# PowerSupply.net
KiCad netlist of a schematic drawn in Altium Designer
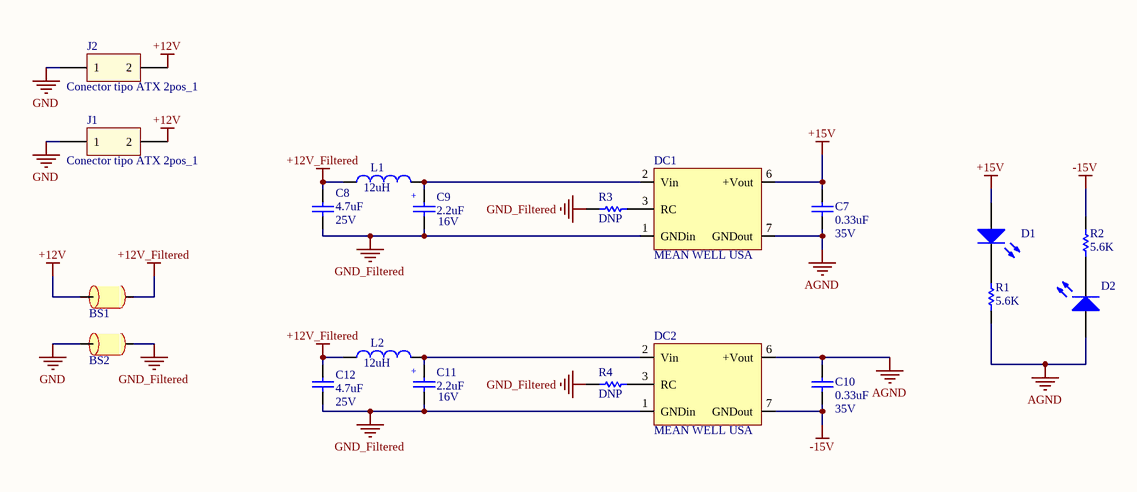
[diagram p0: PowerSupply.SchDoc]

(export (version "E")
  (design (tool "Eeschema 10.0.6"))
  (components
    (comp (ref "BS1")
      (value "Ferrite bead")
      (footprint "RES_1206")
      (description "4A")
      (libsource (lib "Componentes_SOC") (part "Bead"))
    )
    (comp (ref "BS2")
      (value "Ferrite bead")
      (footprint "RES_1206")
      (description "4A")
      (libsource (lib "Componentes_SOC") (part "Bead"))
    )
    (comp (ref "C7")
      (value "0.33uF")
      (footprint "CAP_0603")
      (description "Capacitor Ceramic")
      (fields (field (name "VOLTAGE") "35V"))
      (libsource (lib "Componentes_SOC") (part "Cap_0603"))
    )
    (comp (ref "C8")
      (value "4.7uF")
      (footprint "CAP_0805")
      (description "Capacitor")
      (fields (field (name "VOLTAGE") "25V"))
      (libsource (lib "Componentes_SOC") (part "Cap_0805"))
    )
    (comp (ref "C9")
      (value "2.2uF")
      (footprint "CAP_1206 Tantalio")
      (description "Capacitor Tantalio")
      (fields (field (name "VOLTAGE") "16V"))
      (libsource (lib "Componentes_SOC") (part "Cap Tantalio 1206"))
    )
    (comp (ref "C10")
      (value "0.33uF")
      (footprint "CAP_0603")
      (description "Capacitor Ceramic")
      (fields (field (name "VOLTAGE") "35V"))
      (libsource (lib "Componentes_SOC") (part "Cap_0603"))
    )
    (comp (ref "C11")
      (value "2.2uF")
      (footprint "CAP_1206 Tantalio")
      (description "Capacitor Tantalio")
      (fields (field (name "VOLTAGE") "16V"))
      (libsource (lib "Componentes_SOC") (part "Cap Tantalio 1206"))
    )
    (comp (ref "C12")
      (value "4.7uF")
      (footprint "CAP_0805")
      (description "Capacitor")
      (fields (field (name "VOLTAGE") "25V"))
      (libsource (lib "Componentes_SOC") (part "Cap_0805"))
    )
    (comp (ref "D1")
      (value "LED")
      (footprint "LED_0805_GREEN")
      (description "LED azul")
      (fields (field (name "PUBLISHER") "Altium Limited"))
      (libsource (lib "Componentes_SOC") (part "LED2"))
    )
    (comp (ref "D2")
      (value "LED")
      (footprint "LED_0805_GREEN")
      (description "LED Azul")
      (fields (field (name "PUBLISHER") "Altium Limited"))
      (libsource (lib "Componentes_SOC") (part "LED2"))
    )
    (comp (ref "DC1")
      (value "MEAN WELL USA")
      (footprint "DC/DC 15V 5W")
      (description "Isolated Module DC DC Converter 1 Output 15V 333mA 9V - 18V Input")
      (libsource (lib "Componentes_SOC") (part "DC/DC +12V a +15V 5W"))
    )
    (comp (ref "DC2")
      (value "MEAN WELL USA")
      (footprint "DC/DC 15V 5W")
      (description "Isolated Module DC DC Converter 1 Output 15V 333mA 9V - 18V Input")
      (libsource (lib "Componentes_SOC") (part "DC/DC +12V a +15V 5W"))
    )
    (comp (ref "J1")
      (value "Conector tipo ATX 2pos_1")
      (footprint "Conector tipo ATX Wurth 2 posiciones - (5.5mm)")
      (description "CONN HEADER VERT 2POS 5.5MM")
      (libsource (lib "Componentes_SOC") (part "Conector tipo ATX 2pos_1"))
    )
    (comp (ref "J2")
      (value "Conector tipo ATX 2pos_1")
      (footprint "Conector tipo ATX Wurth 2 posiciones - (5.5mm)")
      (description "CONN HEADER VERT 2POS 5.5MM")
      (libsource (lib "Componentes_SOC") (part "Conector tipo ATX 2pos_1"))
    )
    (comp (ref "L1")
      (value "12uH")
      (footprint "INDUCTOR_0805")
      (description "200mA")
      (libsource (lib "Componentes_SOC") (part "Inductor_0805"))
    )
    (comp (ref "L2")
      (value "12uH")
      (footprint "INDUCTOR_0805")
      (description "200mA")
      (libsource (lib "Componentes_SOC") (part "Inductor_0805"))
    )
    (comp (ref "R1")
      (value "5.6K")
      (footprint "RES_0805")
      (fields (field (name "PUBLISHER") "Altium Limited"))
      (libsource (lib "Componentes_SOC") (part "Res0805"))
    )
    (comp (ref "R2")
      (value "5.6K")
      (footprint "RES_0805")
      (fields (field (name "PUBLISHER") "Altium Limited"))
      (libsource (lib "Componentes_SOC") (part "Res0805"))
    )
    (comp (ref "R3")
      (value "DNP")
      (footprint "RES_0603")
      (libsource (lib "Componentes_SOC") (part "Res0603"))
    )
    (comp (ref "R4")
      (value "DNP")
      (footprint "RES_0603")
      (libsource (lib "Componentes_SOC") (part "Res0603"))
    )
  )
  (nets
    (net (code "1") (name "+12V") (class "Default")
      (node (ref "BS1") (pin "1") (pintype "passive"))
      (node (ref "J1") (pin "2") (pinfunction "2_2") (pintype "passive"))
      (node (ref "J2") (pin "2") (pinfunction "2_2") (pintype "passive"))
    )
    (net (code "2") (name "+12V_Filtered") (class "Default")
      (node (ref "BS1") (pin "2") (pintype "passive"))
      (node (ref "C12") (pin "1") (pinfunction "1_1") (pintype "passive"))
      (node (ref "C8") (pin "1") (pinfunction "1_1") (pintype "passive"))
      (node (ref "L1") (pin "1") (pinfunction "1_1") (pintype "passive"))
      (node (ref "L2") (pin "1") (pinfunction "1_1") (pintype "passive"))
    )
    (net (code "3") (name "+15V") (class "Default")
      (node (ref "C7") (pin "1") (pinfunction "1_1") (pintype "passive"))
      (node (ref "D1") (pin "1") (pinfunction "A_1") (pintype "passive"))
      (node (ref "DC1") (pin "6") (pinfunction "+Vout_6") (pintype "passive"))
    )
    (net (code "4") (name "-15V") (class "Default")
      (node (ref "C10") (pin "2") (pinfunction "2_2") (pintype "passive"))
      (node (ref "DC2") (pin "7") (pinfunction "GNDout_7") (pintype "passive"))
      (node (ref "R2") (pin "2") (pinfunction "2_2") (pintype "passive"))
    )
    (net (code "5") (name "AGND") (class "Default")
      (node (ref "C10") (pin "1") (pinfunction "1_1") (pintype "passive"))
      (node (ref "C7") (pin "2") (pinfunction "2_2") (pintype "passive"))
      (node (ref "D2") (pin "1") (pinfunction "A_1") (pintype "passive"))
      (node (ref "DC1") (pin "7") (pinfunction "GNDout_7") (pintype "passive"))
      (node (ref "DC2") (pin "6") (pinfunction "+Vout_6") (pintype "passive"))
      (node (ref "R1") (pin "1") (pinfunction "1_1") (pintype "passive"))
    )
    (net (code "6") (name "GND") (class "Default")
      (node (ref "BS2") (pin "1") (pintype "passive"))
      (node (ref "J1") (pin "1") (pinfunction "1_1") (pintype "passive"))
      (node (ref "J2") (pin "1") (pinfunction "1_1") (pintype "passive"))
    )
    (net (code "7") (name "GND_Filtered") (class "Default")
      (node (ref "BS2") (pin "2") (pintype "passive"))
      (node (ref "C11") (pin "2") (pinfunction "2_2") (pintype "passive"))
      (node (ref "C12") (pin "2") (pinfunction "2_2") (pintype "passive"))
      (node (ref "C8") (pin "2") (pinfunction "2_2") (pintype "passive"))
      (node (ref "C9") (pin "2") (pinfunction "2_2") (pintype "passive"))
      (node (ref "DC1") (pin "1") (pinfunction "GNDin_1") (pintype "passive"))
      (node (ref "DC2") (pin "1") (pinfunction "GNDin_1") (pintype "passive"))
      (node (ref "R3") (pin "2") (pinfunction "2_2") (pintype "passive"))
      (node (ref "R4") (pin "2") (pinfunction "2_2") (pintype "passive"))
    )
    (net (code "8") (name "Net-(D1-K)") (class "Default")
      (node (ref "D1") (pin "2") (pinfunction "K_2") (pintype "passive"))
      (node (ref "R1") (pin "2") (pinfunction "2_2") (pintype "passive"))
    )
    (net (code "9") (name "Net-(D2-K)") (class "Default")
      (node (ref "D2") (pin "2") (pinfunction "K_2") (pintype "passive"))
      (node (ref "R2") (pin "1") (pinfunction "1_1") (pintype "passive"))
    )
    (net (code "10") (name "Net-(DC1-RC)") (class "Default")
      (node (ref "DC1") (pin "3") (pinfunction "RC_3") (pintype "passive"))
      (node (ref "R3") (pin "1") (pinfunction "1_1") (pintype "passive"))
    )
    (net (code "11") (name "Net-(DC1-Vin)") (class "Default")
      (node (ref "C9") (pin "1") (pinfunction "1_1") (pintype "passive"))
      (node (ref "DC1") (pin "2") (pinfunction "Vin_2") (pintype "passive"))
      (node (ref "L1") (pin "2") (pinfunction "2_2") (pintype "passive"))
    )
    (net (code "12") (name "Net-(DC2-RC)") (class "Default")
      (node (ref "DC2") (pin "3") (pinfunction "RC_3") (pintype "passive"))
      (node (ref "R4") (pin "1") (pinfunction "1_1") (pintype "passive"))
    )
    (net (code "13") (name "Net-(DC2-Vin)") (class "Default")
      (node (ref "C11") (pin "1") (pinfunction "1_1") (pintype "passive"))
      (node (ref "DC2") (pin "2") (pinfunction "Vin_2") (pintype "passive"))
      (node (ref "L2") (pin "2") (pinfunction "2_2") (pintype "passive"))
    )
    (net (code "14") (name "unconnected-(DC1-NC-Pad15)") (class "Default")
      (node (ref "DC1") (pin "15") (pinfunction "NC_15") (pintype "passive"))
    )
    (net (code "15") (name "unconnected-(DC1-NC-Pad16)") (class "Default")
      (node (ref "DC1") (pin "16") (pinfunction "NC_16") (pintype "passive"))
    )
    (net (code "16") (name "unconnected-(DC1-NC-Pad17)") (class "Default")
      (node (ref "DC1") (pin "17") (pinfunction "NC_17") (pintype "passive"))
    )
    (net (code "17") (name "unconnected-(DC1-NC-Pad26)") (class "Default")
      (node (ref "DC1") (pin "26") (pinfunction "NC_26") (pintype "passive"))
    )
    (net (code "18") (name "unconnected-(DC1-NC-Pad27)") (class "Default")
      (node (ref "DC1") (pin "27") (pinfunction "NC_27") (pintype "passive"))
    )
    (net (code "19") (name "unconnected-(DC2-NC-Pad15)") (class "Default")
      (node (ref "DC2") (pin "15") (pinfunction "NC_15") (pintype "passive"))
    )
    (net (code "20") (name "unconnected-(DC2-NC-Pad16)") (class "Default")
      (node (ref "DC2") (pin "16") (pinfunction "NC_16") (pintype "passive"))
    )
    (net (code "21") (name "unconnected-(DC2-NC-Pad17)") (class "Default")
      (node (ref "DC2") (pin "17") (pinfunction "NC_17") (pintype "passive"))
    )
    (net (code "22") (name "unconnected-(DC2-NC-Pad26)") (class "Default")
      (node (ref "DC2") (pin "26") (pinfunction "NC_26") (pintype "passive"))
    )
    (net (code "23") (name "unconnected-(DC2-NC-Pad27)") (class "Default")
      (node (ref "DC2") (pin "27") (pinfunction "NC_27") (pintype "passive"))
    )
  )
)
